# was_not_root_aerialboard_rev1.net
KiCad netlist of a schematic drawn in EAGLE
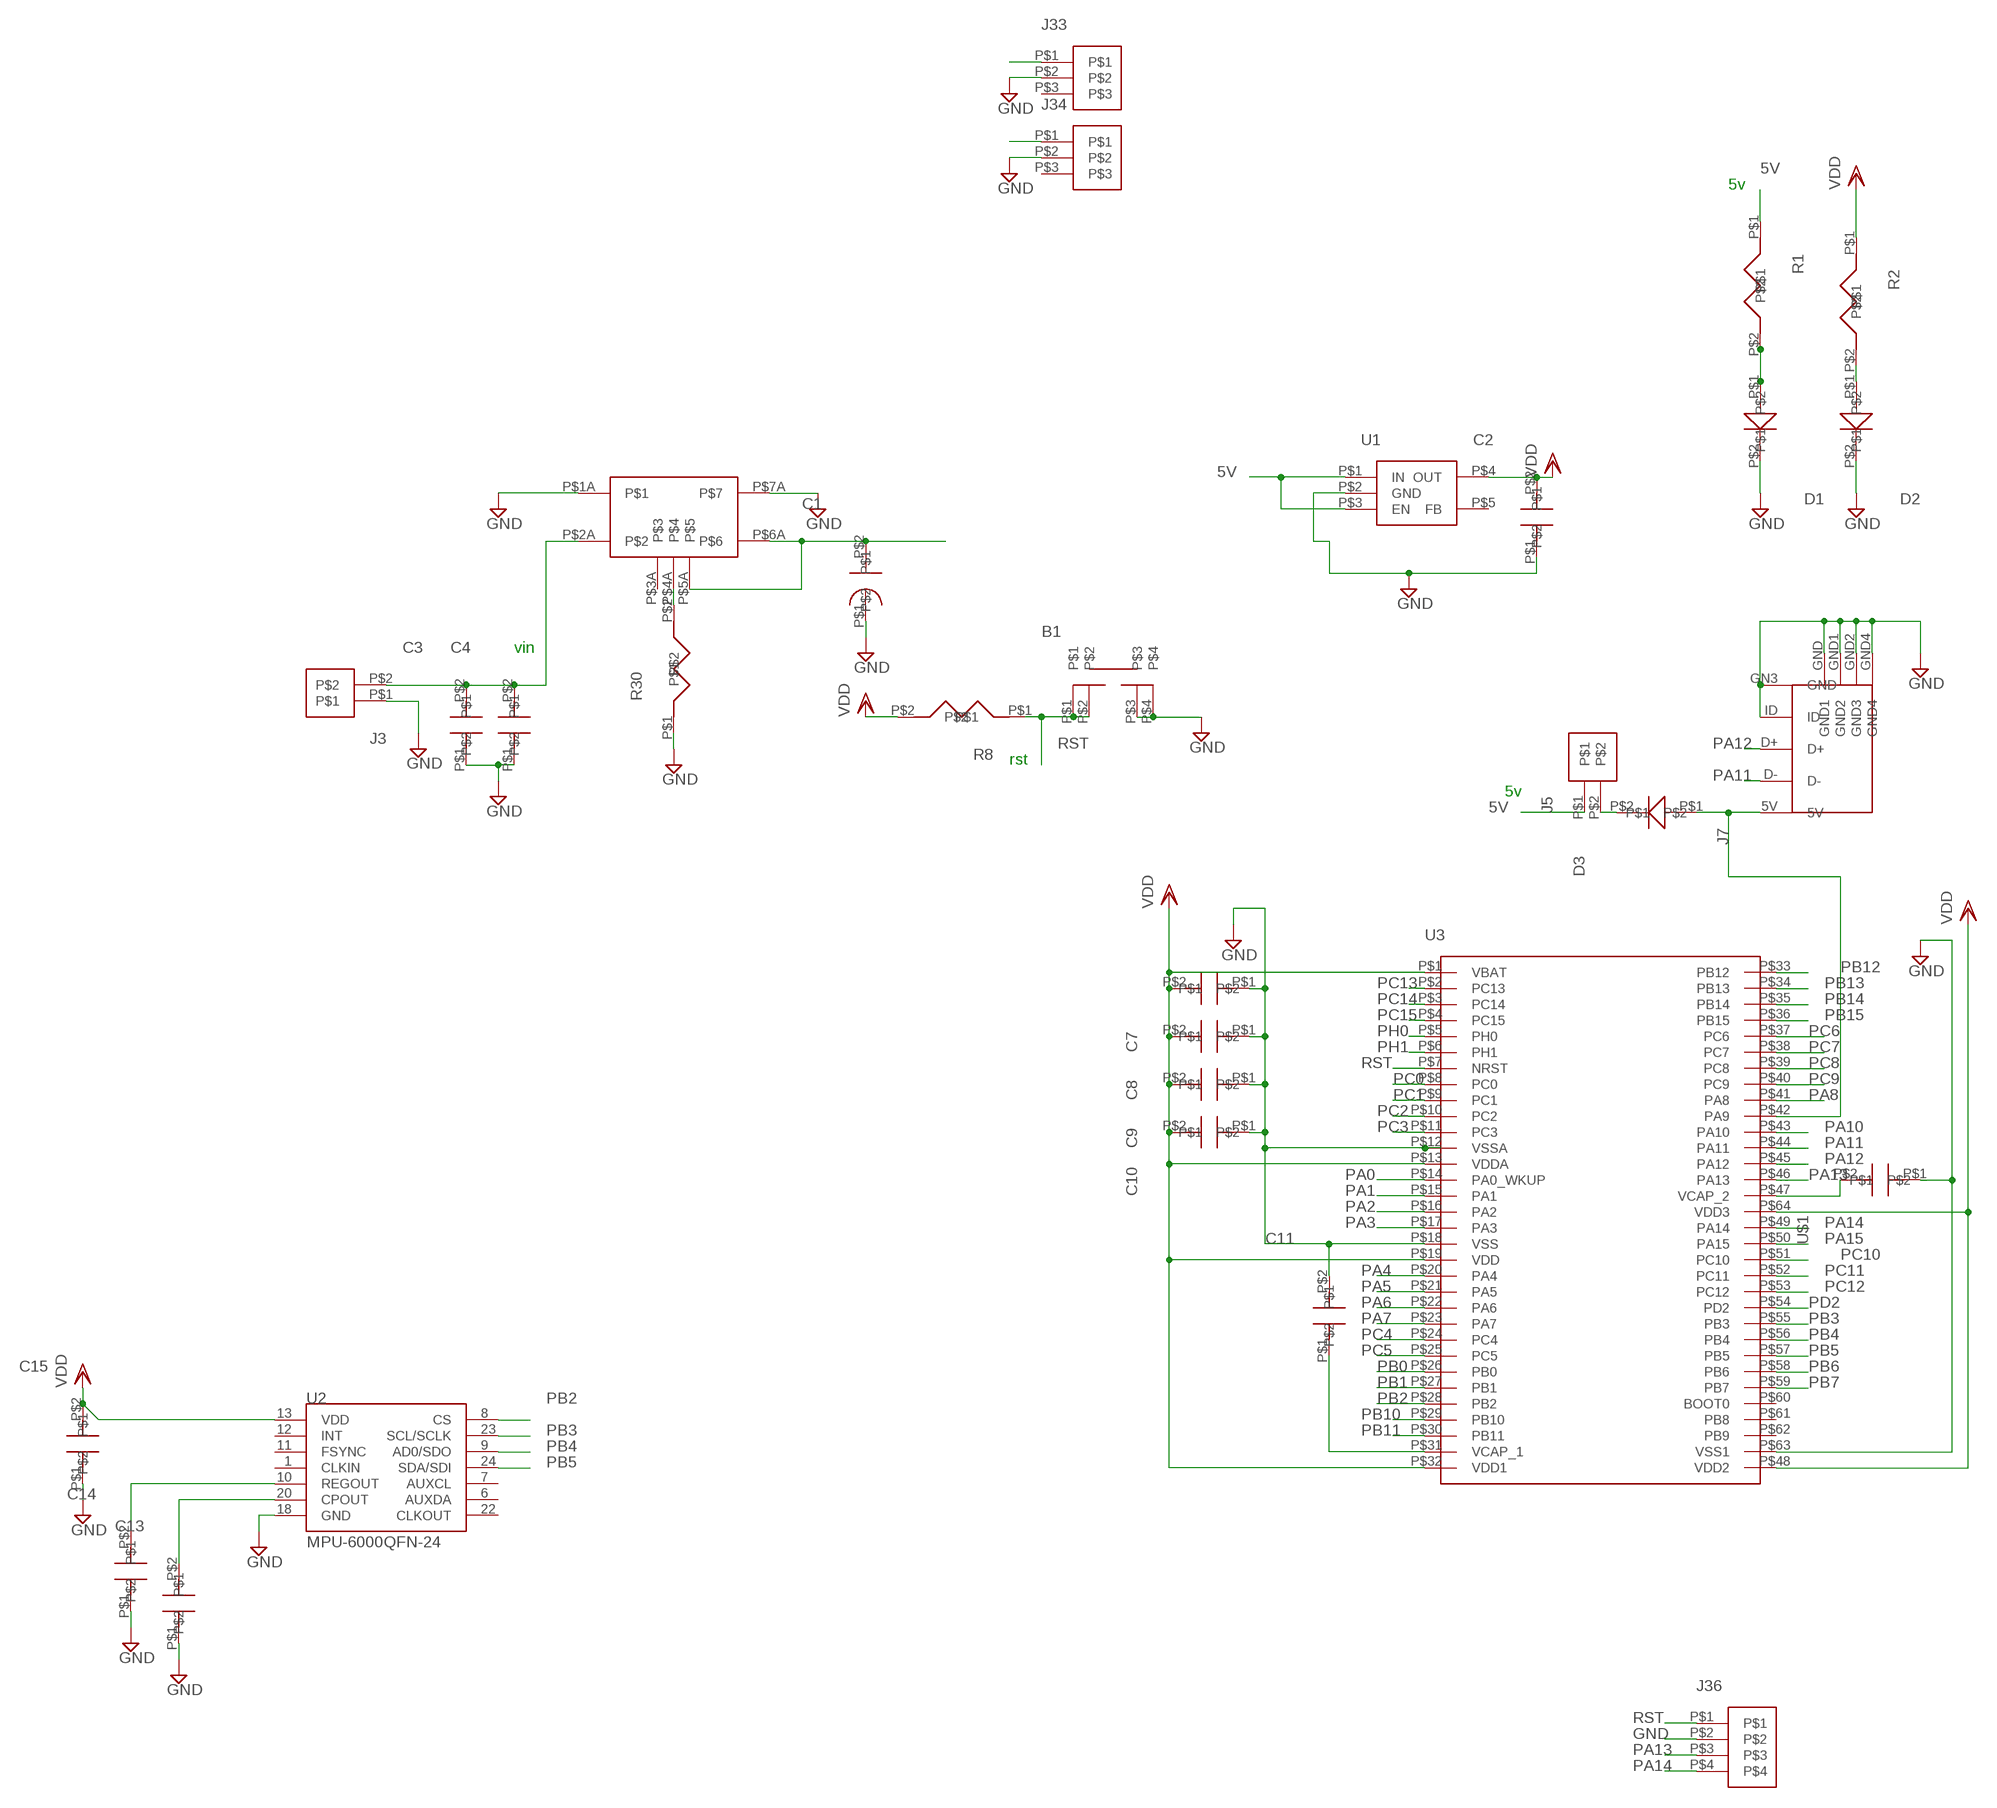
[diagram p0: schematic, sheet 1, part 1 of 2]
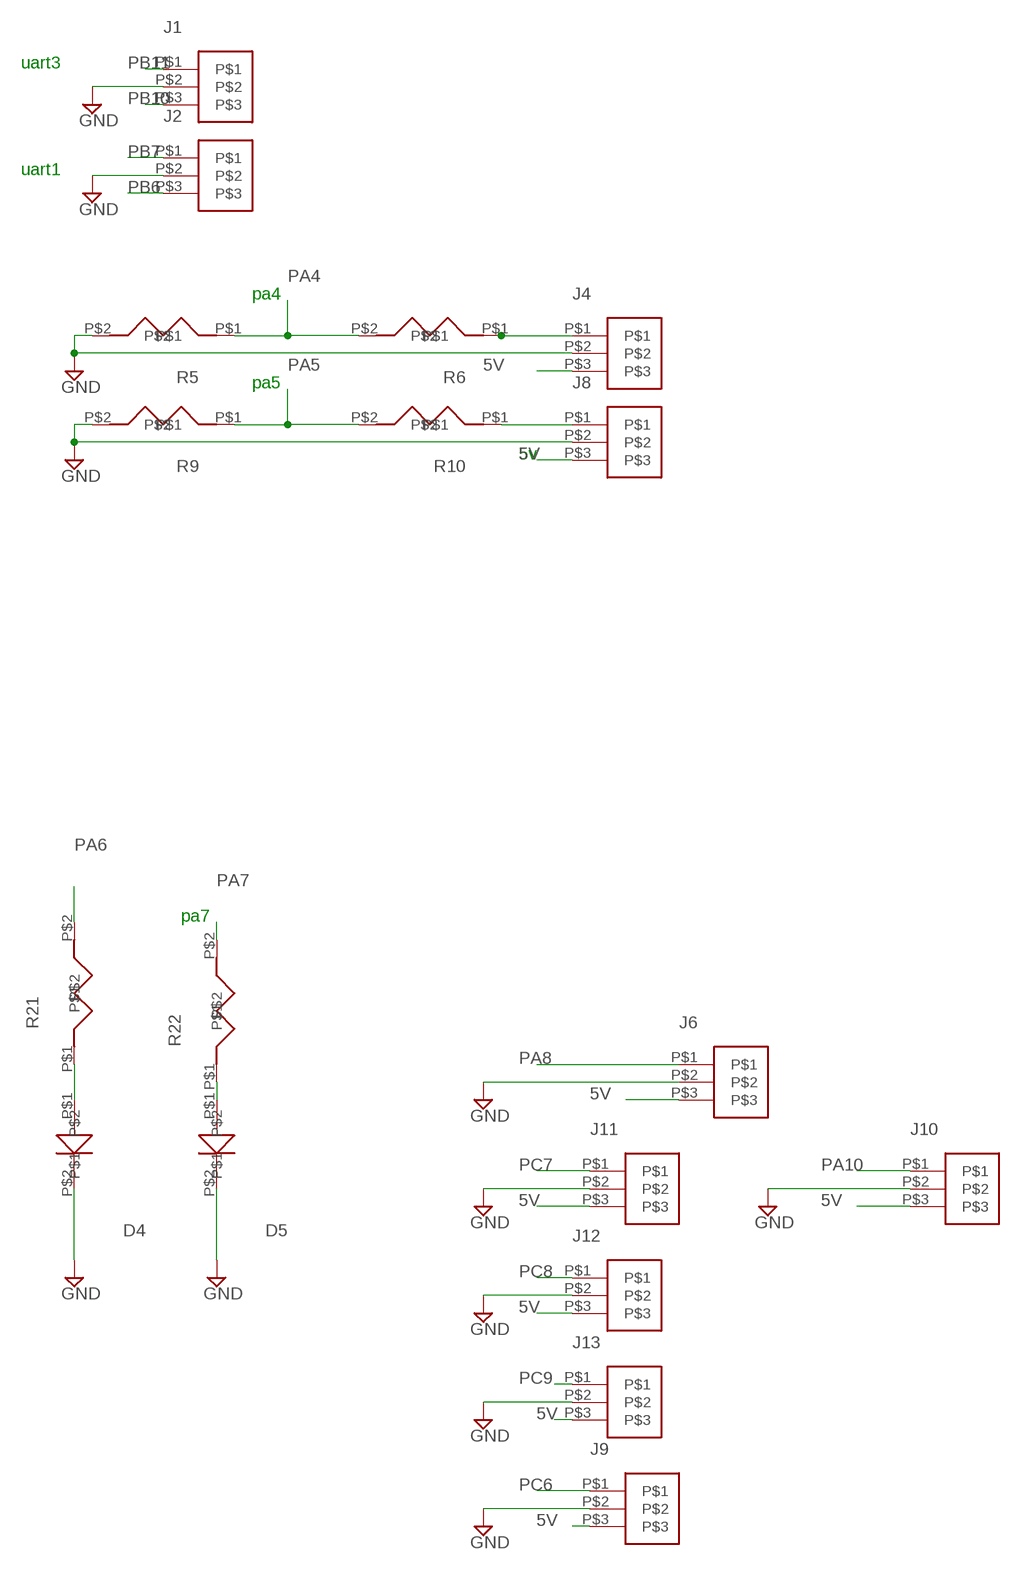
[diagram p1: schematic, sheet 1, part 2 of 2]

(export (version "E")
  (design (tool "Eeschema 10.0.6"))
  (components
    (comp (ref "B1")
      (value "SM-BUTTON")
      (footprint "eagle-import:SM_BUTTON")
      (libsource (lib "eagle-import") (part "SM-BUTTON"))
    )
    (comp (ref "C1")
      (value "CAPACITOR-330UF")
      (footprint "eagle-import:330UF-CAPACITOR")
      (libsource (lib "eagle-import") (part "CAPACITOR-330UF"))
    )
    (comp (ref "C2")
      (value "2.2UF-CAP")
      (footprint "eagle-import:0603-CAPACITOR")
      (libsource (lib "eagle-import") (part "2.2UF-CAP"))
    )
    (comp (ref "C3")
      (value "2.2UF-CAP")
      (footprint "eagle-import:0603-CAPACITOR")
      (libsource (lib "eagle-import") (part "2.2UF-CAP"))
    )
    (comp (ref "C4")
      (value "2.2UF-CAP")
      (footprint "eagle-import:0603-CAPACITOR")
      (libsource (lib "eagle-import") (part "2.2UF-CAP"))
    )
    (comp (ref "C7")
      (value "CAPACITOR-.1UF-4V")
      (footprint "eagle-import:0603-CAPACITOR")
      (libsource (lib "eagle-import") (part "CAPACITOR-.1UF-4V"))
    )
    (comp (ref "C8")
      (value "CAPACITOR-.1UF-4V")
      (footprint "eagle-import:0603-CAPACITOR")
      (libsource (lib "eagle-import") (part "CAPACITOR-.1UF-4V"))
    )
    (comp (ref "C9")
      (value "CAPACITOR-.1UF-4V")
      (footprint "eagle-import:0603-CAPACITOR")
      (libsource (lib "eagle-import") (part "CAPACITOR-.1UF-4V"))
    )
    (comp (ref "C10")
      (value "4.7UF-CAP6.3V")
      (footprint "eagle-import:0603-CAPACITOR")
      (libsource (lib "eagle-import") (part "4.7UF-CAP6.3V"))
    )
    (comp (ref "C11")
      (value "2.2UF-CAP")
      (footprint "eagle-import:0603-CAPACITOR")
      (libsource (lib "eagle-import") (part "2.2UF-CAP"))
    )
    (comp (ref "C13")
      (value "CAPACITOR-2.2NF-50V")
      (footprint "eagle-import:0603-CAPACITOR")
      (libsource (lib "eagle-import") (part "CAPACITOR-2.2NF-50V"))
    )
    (comp (ref "C14")
      (value "CAPACITOR-.1UF-4V")
      (footprint "eagle-import:0603-CAPACITOR")
      (libsource (lib "eagle-import") (part "CAPACITOR-.1UF-4V"))
    )
    (comp (ref "C15")
      (value "CAPACITOR-.1UF-4V")
      (footprint "eagle-import:0603-CAPACITOR")
      (libsource (lib "eagle-import") (part "CAPACITOR-.1UF-4V"))
    )
    (comp (ref "D1")
      (value "RED_LED")
      (footprint "eagle-import:0603-CAPACITOR")
      (libsource (lib "eagle-import") (part "RED_LED"))
    )
    (comp (ref "D2")
      (value "RED_LED")
      (footprint "eagle-import:0603-CAPACITOR")
      (libsource (lib "eagle-import") (part "RED_LED"))
    )
    (comp (ref "D3")
      (value "B240A-DIODE")
      (footprint "eagle-import:DIODE-DS13004")
      (libsource (lib "eagle-import") (part "B240A-DIODE"))
    )
    (comp (ref "D4")
      (value "RED_LED")
      (footprint "eagle-import:0603-CAPACITOR")
      (libsource (lib "eagle-import") (part "RED_LED"))
    )
    (comp (ref "D5")
      (value "ORANGE_LED")
      (footprint "eagle-import:0603-CAPACITOR")
      (libsource (lib "eagle-import") (part "ORANGE_LED"))
    )
    (comp (ref "J1")
      (value "3-PIN-SHERLOCK")
      (footprint "eagle-import:3-PIN-2MM")
      (libsource (lib "eagle-import") (part "3-PIN-SHERLOCK"))
    )
    (comp (ref "J2")
      (value "3-PIN-SHERLOCK")
      (footprint "eagle-import:3-PIN-2MM")
      (libsource (lib "eagle-import") (part "3-PIN-SHERLOCK"))
    )
    (comp (ref "J3")
      (value "2-PIN-POWER")
      (footprint "eagle-import:2-PIN-3MM")
      (libsource (lib "eagle-import") (part "2-PIN-POWER"))
    )
    (comp (ref "J4")
      (value "3-PIN-SHERLOCK")
      (footprint "eagle-import:3-PIN-2MM")
      (libsource (lib "eagle-import") (part "3-PIN-SHERLOCK"))
    )
    (comp (ref "J5")
      (value "2-PIN-100MIL")
      (footprint "eagle-import:2PIN-100MIL")
      (libsource (lib "eagle-import") (part "2-PIN-100MIL"))
    )
    (comp (ref "J6")
      (value "3-PIN-SHERLOCK")
      (footprint "eagle-import:3-PIN-2MM")
      (libsource (lib "eagle-import") (part "3-PIN-SHERLOCK"))
    )
    (comp (ref "J7")
      (value "USB_MINI_B")
      (footprint "eagle-import:USB_MINI_B")
      (libsource (lib "eagle-import") (part "USB_MINI_B"))
    )
    (comp (ref "J8")
      (value "3-PIN-SHERLOCK")
      (footprint "eagle-import:3-PIN-2MM")
      (libsource (lib "eagle-import") (part "3-PIN-SHERLOCK"))
    )
    (comp (ref "J9")
      (value "3-PIN-SHERLOCK")
      (footprint "eagle-import:3-PIN-2MM")
      (libsource (lib "eagle-import") (part "3-PIN-SHERLOCK"))
    )
    (comp (ref "J10")
      (value "3-PIN-SHERLOCK")
      (footprint "eagle-import:3-PIN-2MM")
      (libsource (lib "eagle-import") (part "3-PIN-SHERLOCK"))
    )
    (comp (ref "J11")
      (value "3-PIN-SHERLOCK")
      (footprint "eagle-import:3-PIN-2MM")
      (libsource (lib "eagle-import") (part "3-PIN-SHERLOCK"))
    )
    (comp (ref "J12")
      (value "3-PIN-SHERLOCK")
      (footprint "eagle-import:3-PIN-2MM")
      (libsource (lib "eagle-import") (part "3-PIN-SHERLOCK"))
    )
    (comp (ref "J13")
      (value "3-PIN-SHERLOCK")
      (footprint "eagle-import:3-PIN-2MM")
      (libsource (lib "eagle-import") (part "3-PIN-SHERLOCK"))
    )
    (comp (ref "J33")
      (value "3-PIN-3MM")
      (footprint "eagle-import:3-PIN-3MM")
      (libsource (lib "eagle-import") (part "3-PIN-3MM"))
    )
    (comp (ref "J34")
      (value "3-PIN-3MM")
      (footprint "eagle-import:3-PIN-3MM")
      (libsource (lib "eagle-import") (part "3-PIN-3MM"))
    )
    (comp (ref "J36")
      (value "4-PIN-SHERLOCK")
      (footprint "eagle-import:4-PIN-2MM")
      (libsource (lib "eagle-import") (part "4-PIN-SHERLOCK"))
    )
    (comp (ref "R1")
      (value "RESISTOR-4.7K-25V")
      (footprint "eagle-import:0603-CAPACITOR")
      (libsource (lib "eagle-import") (part "RESISTOR-4.7K-25V"))
    )
    (comp (ref "R2")
      (value "RESISTOR-4.7K-25V")
      (footprint "eagle-import:0603-CAPACITOR")
      (libsource (lib "eagle-import") (part "RESISTOR-4.7K-25V"))
    )
    (comp (ref "R5")
      (value "10K_RESISTOR")
      (footprint "eagle-import:0603-CAPACITOR")
      (libsource (lib "eagle-import") (part "10K_RESISTOR"))
    )
    (comp (ref "R6")
      (value "10K_RESISTOR")
      (footprint "eagle-import:0603-CAPACITOR")
      (libsource (lib "eagle-import") (part "10K_RESISTOR"))
    )
    (comp (ref "R8")
      (value "RESISTOR-4.7K-25V")
      (footprint "eagle-import:0603-CAPACITOR")
      (libsource (lib "eagle-import") (part "RESISTOR-4.7K-25V"))
    )
    (comp (ref "R9")
      (value "10K_RESISTOR")
      (footprint "eagle-import:0603-CAPACITOR")
      (libsource (lib "eagle-import") (part "10K_RESISTOR"))
    )
    (comp (ref "R10")
      (value "10K_RESISTOR")
      (footprint "eagle-import:0603-CAPACITOR")
      (libsource (lib "eagle-import") (part "10K_RESISTOR"))
    )
    (comp (ref "R21")
      (value "RESISTOR-4.7K-25V")
      (footprint "eagle-import:0603-CAPACITOR")
      (libsource (lib "eagle-import") (part "RESISTOR-4.7K-25V"))
    )
    (comp (ref "R22")
      (value "RESISTOR-4.7K-25V")
      (footprint "eagle-import:0603-CAPACITOR")
      (libsource (lib "eagle-import") (part "RESISTOR-4.7K-25V"))
    )
    (comp (ref "R30")
      (value "21K_RESISTOR")
      (footprint "eagle-import:0603-CAPACITOR")
      (libsource (lib "eagle-import") (part "21K_RESISTOR"))
    )
    (comp (ref "U$1")
      (value "2.2UF-CAP")
      (footprint "eagle-import:0603-CAPACITOR")
      (libsource (lib "eagle-import") (part "2.2UF-CAP"))
    )
    (comp (ref "U$2")
      (value "WIDE_IN_REG")
      (footprint "eagle-import:WIDE_IN_REG")
      (libsource (lib "eagle-import") (part "WIDE_IN_REG"))
    )
    (comp (ref "U1")
      (value "TPS73433-3.3-REG")
      (footprint "eagle-import:TPS73433-SOT5")
      (libsource (lib "eagle-import") (part "TPS73433-3.3-REG"))
    )
    (comp (ref "U2")
      (value "MPU-6000QFN-24")
      (footprint "eagle-import:QFN-24-TESTING")
      (libsource (lib "eagle-import") (part "MPU-6000QFN-24"))
    )
    (comp (ref "U3")
      (value "STM32F405RG")
      (footprint "eagle-import:LQFP-64-STM32F405")
      (libsource (lib "eagle-import") (part "STM32F405RG"))
    )
  )
  (nets
    (net (code "1") (name "/5V") (class "Default")
      (node (ref "C1") (pin "P$2") (pinfunction "P$2_P$2") (pintype "bidirectional"))
      (node (ref "J10") (pin "P$3") (pinfunction "P$3_P$3") (pintype "bidirectional"))
      (node (ref "J11") (pin "P$3") (pinfunction "P$3_P$3") (pintype "bidirectional"))
      (node (ref "J12") (pin "P$3") (pinfunction "P$3_P$3") (pintype "bidirectional"))
      (node (ref "J13") (pin "P$3") (pinfunction "P$3_P$3") (pintype "bidirectional"))
      (node (ref "J33") (pin "P$1") (pinfunction "P$1_P$1") (pintype "bidirectional"))
      (node (ref "J34") (pin "P$1") (pinfunction "P$1_P$1") (pintype "bidirectional"))
      (node (ref "J4") (pin "P$3") (pinfunction "P$3_P$3") (pintype "bidirectional"))
      (node (ref "J5") (pin "P$1") (pinfunction "P$1_P$1") (pintype "bidirectional"))
      (node (ref "J6") (pin "P$3") (pinfunction "P$3_P$3") (pintype "bidirectional"))
      (node (ref "J8") (pin "P$3") (pinfunction "P$3_P$3") (pintype "bidirectional"))
      (node (ref "J9") (pin "P$3") (pinfunction "P$3_P$3") (pintype "bidirectional"))
      (node (ref "R1") (pin "P$1") (pinfunction "P$1_P$1") (pintype "bidirectional"))
      (node (ref "U$2") (pin "P$5A") (pinfunction "P$5_P$5A") (pintype "bidirectional"))
      (node (ref "U$2") (pin "P$6A") (pinfunction "P$6_P$6A") (pintype "bidirectional"))
      (node (ref "U1") (pin "P$1") (pinfunction "IN_P$1") (pintype "bidirectional"))
      (node (ref "U1") (pin "P$3") (pinfunction "EN_P$3") (pintype "bidirectional"))
    )
    (net (code "2") (name "/PA0") (class "Default")
      (node (ref "U3") (pin "P$14") (pinfunction "PA0_WKUP_P$14") (pintype "bidirectional"))
    )
    (net (code "3") (name "/PA1") (class "Default")
      (node (ref "U3") (pin "P$15") (pinfunction "PA1_P$15") (pintype "bidirectional"))
    )
    (net (code "4") (name "/PA2") (class "Default")
      (node (ref "U3") (pin "P$16") (pinfunction "PA2_P$16") (pintype "bidirectional"))
    )
    (net (code "5") (name "/PA3") (class "Default")
      (node (ref "U3") (pin "P$17") (pinfunction "PA3_P$17") (pintype "bidirectional"))
    )
    (net (code "6") (name "/PA4") (class "Default")
      (node (ref "R5") (pin "P$1") (pinfunction "P$1_P$1") (pintype "bidirectional"))
      (node (ref "R6") (pin "P$2") (pinfunction "P$2_P$2") (pintype "bidirectional"))
      (node (ref "U3") (pin "P$20") (pinfunction "PA4_P$20") (pintype "bidirectional"))
    )
    (net (code "7") (name "/PA5") (class "Default")
      (node (ref "R10") (pin "P$2") (pinfunction "P$2_P$2") (pintype "bidirectional"))
      (node (ref "R9") (pin "P$1") (pinfunction "P$1_P$1") (pintype "bidirectional"))
      (node (ref "U3") (pin "P$21") (pinfunction "PA5_P$21") (pintype "bidirectional"))
    )
    (net (code "8") (name "/PA6") (class "Default")
      (node (ref "R21") (pin "P$2") (pinfunction "P$2_P$2") (pintype "bidirectional"))
      (node (ref "U3") (pin "P$22") (pinfunction "PA6_P$22") (pintype "bidirectional"))
    )
    (net (code "9") (name "/PA7") (class "Default")
      (node (ref "R22") (pin "P$2") (pinfunction "P$2_P$2") (pintype "bidirectional"))
      (node (ref "U3") (pin "P$23") (pinfunction "PA7_P$23") (pintype "bidirectional"))
    )
    (net (code "10") (name "/PA8") (class "Default")
      (node (ref "J6") (pin "P$1") (pinfunction "P$1_P$1") (pintype "bidirectional"))
      (node (ref "U3") (pin "P$41") (pinfunction "PA8_P$41") (pintype "bidirectional"))
    )
    (net (code "11") (name "/PA10") (class "Default")
      (node (ref "J10") (pin "P$1") (pinfunction "P$1_P$1") (pintype "bidirectional"))
      (node (ref "U3") (pin "P$43") (pinfunction "PA10_P$43") (pintype "bidirectional"))
    )
    (net (code "12") (name "/PA11") (class "Default")
      (node (ref "J7") (pin "D-") (pinfunction "D-_D-") (pintype "bidirectional"))
      (node (ref "U3") (pin "P$44") (pinfunction "PA11_P$44") (pintype "bidirectional"))
    )
    (net (code "13") (name "/PA12") (class "Default")
      (node (ref "J7") (pin "D+") (pinfunction "D+_D+") (pintype "bidirectional"))
      (node (ref "U3") (pin "P$45") (pinfunction "PA12_P$45") (pintype "bidirectional"))
    )
    (net (code "14") (name "/PA13") (class "Default")
      (node (ref "J36") (pin "P$3") (pinfunction "P$3_P$3") (pintype "bidirectional"))
      (node (ref "U3") (pin "P$46") (pinfunction "PA13_P$46") (pintype "bidirectional"))
    )
    (net (code "15") (name "/PA14") (class "Default")
      (node (ref "J36") (pin "P$4") (pinfunction "P$4_P$4") (pintype "bidirectional"))
      (node (ref "U3") (pin "P$49") (pinfunction "PA14_P$49") (pintype "bidirectional"))
    )
    (net (code "16") (name "/PA15") (class "Default")
      (node (ref "U3") (pin "P$50") (pinfunction "PA15_P$50") (pintype "bidirectional"))
    )
    (net (code "17") (name "/PB0") (class "Default")
      (node (ref "U3") (pin "P$26") (pinfunction "PB0_P$26") (pintype "bidirectional"))
    )
    (net (code "18") (name "/PB1") (class "Default")
      (node (ref "U3") (pin "P$27") (pinfunction "PB1_P$27") (pintype "bidirectional"))
    )
    (net (code "19") (name "/PB2") (class "Default")
      (node (ref "U2") (pin "8") (pinfunction "CS_8") (pintype "bidirectional"))
      (node (ref "U3") (pin "P$28") (pinfunction "PB2_P$28") (pintype "bidirectional"))
    )
    (net (code "20") (name "/PB3") (class "Default")
      (node (ref "U2") (pin "23") (pinfunction "SCL/SCLK_23") (pintype "bidirectional"))
      (node (ref "U3") (pin "P$55") (pinfunction "PB3_P$55") (pintype "bidirectional"))
    )
    (net (code "21") (name "/PB4") (class "Default")
      (node (ref "U2") (pin "9") (pinfunction "AD0/SDO_9") (pintype "bidirectional"))
      (node (ref "U3") (pin "P$56") (pinfunction "PB4_P$56") (pintype "bidirectional"))
    )
    (net (code "22") (name "/PB5") (class "Default")
      (node (ref "U2") (pin "24") (pinfunction "SDA/SDI_24") (pintype "bidirectional"))
      (node (ref "U3") (pin "P$57") (pinfunction "PB5_P$57") (pintype "bidirectional"))
    )
    (net (code "23") (name "/PB6") (class "Default")
      (node (ref "J2") (pin "P$3") (pinfunction "P$3_P$3") (pintype "bidirectional"))
      (node (ref "U3") (pin "P$58") (pinfunction "PB6_P$58") (pintype "bidirectional"))
    )
    (net (code "24") (name "/PB7") (class "Default")
      (node (ref "J2") (pin "P$1") (pinfunction "P$1_P$1") (pintype "bidirectional"))
      (node (ref "U3") (pin "P$59") (pinfunction "PB7_P$59") (pintype "bidirectional"))
    )
    (net (code "25") (name "/PB10") (class "Default")
      (node (ref "J1") (pin "P$3") (pinfunction "P$3_P$3") (pintype "bidirectional"))
      (node (ref "U3") (pin "P$29") (pinfunction "PB10_P$29") (pintype "bidirectional"))
    )
    (net (code "26") (name "/PB11") (class "Default")
      (node (ref "J1") (pin "P$1") (pinfunction "P$1_P$1") (pintype "bidirectional"))
      (node (ref "U3") (pin "P$30") (pinfunction "PB11_P$30") (pintype "bidirectional"))
    )
    (net (code "27") (name "/PB12") (class "Default")
      (node (ref "U3") (pin "P$33") (pinfunction "PB12_P$33") (pintype "bidirectional"))
    )
    (net (code "28") (name "/PB13") (class "Default")
      (node (ref "U3") (pin "P$34") (pinfunction "PB13_P$34") (pintype "bidirectional"))
    )
    (net (code "29") (name "/PB14") (class "Default")
      (node (ref "U3") (pin "P$35") (pinfunction "PB14_P$35") (pintype "bidirectional"))
    )
    (net (code "30") (name "/PB15") (class "Default")
      (node (ref "U3") (pin "P$36") (pinfunction "PB15_P$36") (pintype "bidirectional"))
    )
    (net (code "31") (name "/PC0") (class "Default")
      (node (ref "U3") (pin "P$8") (pinfunction "PC0_P$8") (pintype "bidirectional"))
    )
    (net (code "32") (name "/PC1") (class "Default")
      (node (ref "U3") (pin "P$9") (pinfunction "PC1_P$9") (pintype "bidirectional"))
    )
    (net (code "33") (name "/PC2") (class "Default")
      (node (ref "U3") (pin "P$10") (pinfunction "PC2_P$10") (pintype "bidirectional"))
    )
    (net (code "34") (name "/PC3") (class "Default")
      (node (ref "U3") (pin "P$11") (pinfunction "PC3_P$11") (pintype "bidirectional"))
    )
    (net (code "35") (name "/PC4") (class "Default")
      (node (ref "U3") (pin "P$24") (pinfunction "PC4_P$24") (pintype "bidirectional"))
    )
    (net (code "36") (name "/PC5") (class "Default")
      (node (ref "U3") (pin "P$25") (pinfunction "PC5_P$25") (pintype "bidirectional"))
    )
    (net (code "37") (name "/PC6") (class "Default")
      (node (ref "J9") (pin "P$1") (pinfunction "P$1_P$1") (pintype "bidirectional"))
      (node (ref "U3") (pin "P$37") (pinfunction "PC6_P$37") (pintype "bidirectional"))
    )
    (net (code "38") (name "/PC7") (class "Default")
      (node (ref "J11") (pin "P$1") (pinfunction "P$1_P$1") (pintype "bidirectional"))
      (node (ref "U3") (pin "P$38") (pinfunction "PC7_P$38") (pintype "bidirectional"))
    )
    (net (code "39") (name "/PC8") (class "Default")
      (node (ref "J12") (pin "P$1") (pinfunction "P$1_P$1") (pintype "bidirectional"))
      (node (ref "U3") (pin "P$39") (pinfunction "PC8_P$39") (pintype "bidirectional"))
    )
    (net (code "40") (name "/PC9") (class "Default")
      (node (ref "J13") (pin "P$1") (pinfunction "P$1_P$1") (pintype "bidirectional"))
      (node (ref "U3") (pin "P$40") (pinfunction "PC9_P$40") (pintype "bidirectional"))
    )
    (net (code "41") (name "/PC10") (class "Default")
      (node (ref "U3") (pin "P$51") (pinfunction "PC10_P$51") (pintype "bidirectional"))
    )
    (net (code "42") (name "/PC11") (class "Default")
      (node (ref "U3") (pin "P$52") (pinfunction "PC11_P$52") (pintype "bidirectional"))
    )
    (net (code "43") (name "/PC12") (class "Default")
      (node (ref "U3") (pin "P$53") (pinfunction "PC12_P$53") (pintype "bidirectional"))
    )
    (net (code "44") (name "/PC13") (class "Default")
      (node (ref "U3") (pin "P$2") (pinfunction "PC13_P$2") (pintype "bidirectional"))
    )
    (net (code "45") (name "/PC14") (class "Default")
      (node (ref "U3") (pin "P$3") (pinfunction "PC14_P$3") (pintype "bidirectional"))
    )
    (net (code "46") (name "/PC15") (class "Default")
      (node (ref "U3") (pin "P$4") (pinfunction "PC15_P$4") (pintype "bidirectional"))
    )
    (net (code "47") (name "/PD2") (class "Default")
      (node (ref "U3") (pin "P$54") (pinfunction "PD2_P$54") (pintype "bidirectional"))
    )
    (net (code "48") (name "/PH0") (class "Default")
      (node (ref "U3") (pin "P$5") (pinfunction "PH0_P$5") (pintype "bidirectional"))
    )
    (net (code "49") (name "/PH1") (class "Default")
      (node (ref "U3") (pin "P$6") (pinfunction "PH1_P$6") (pintype "bidirectional"))
    )
    (net (code "50") (name "/RST") (class "Default")
      (node (ref "B1") (pin "P$1") (pinfunction "P$1_P$1") (pintype "bidirectional"))
      (node (ref "B1") (pin "P$2") (pinfunction "P$2_P$2") (pintype "bidirectional"))
      (node (ref "J36") (pin "P$1") (pinfunction "P$1_P$1") (pintype "bidirectional"))
      (node (ref "R8") (pin "P$1") (pinfunction "P$1_P$1") (pintype "bidirectional"))
      (node (ref "U3") (pin "P$7") (pinfunction "NRST_P$7") (pintype "bidirectional"))
    )
    (net (code "51") (name "GND") (class "Default")
      (node (ref "B1") (pin "P$3") (pinfunction "P$3_P$3") (pintype "bidirectional"))
      (node (ref "B1") (pin "P$4") (pinfunction "P$4_P$4") (pintype "bidirectional"))
      (node (ref "C1") (pin "P$1") (pinfunction "P$1_P$1") (pintype "bidirectional"))
      (node (ref "C10") (pin "P$1") (pinfunction "P$1_P$1") (pintype "bidirectional"))
      (node (ref "C11") (pin "P$2") (pinfunction "P$2_P$2") (pintype "bidirectional"))
      (node (ref "C13") (pin "P$1") (pinfunction "P$1_P$1") (pintype "bidirectional"))
      (node (ref "C14") (pin "P$1") (pinfunction "P$1_P$1") (pintype "bidirectional"))
      (node (ref "C15") (pin "P$1") (pinfunction "P$1_P$1") (pintype "bidirectional"))
      (node (ref "C2") (pin "P$1") (pinfunction "P$1_P$1") (pintype "bidirectional"))
      (node (ref "C3") (pin "P$1") (pinfunction "P$1_P$1") (pintype "bidirectional"))
      (node (ref "C4") (pin "P$1") (pinfunction "P$1_P$1") (pintype "bidirectional"))
      (node (ref "C7") (pin "P$1") (pinfunction "P$1_P$1") (pintype "bidirectional"))
      (node (ref "C8") (pin "P$1") (pinfunction "P$1_P$1") (pintype "bidirectional"))
      (node (ref "C9") (pin "P$1") (pinfunction "P$1_P$1") (pintype "bidirectional"))
      (node (ref "D1") (pin "P$2") (pinfunction "P$2_P$2") (pintype "bidirectional"))
      (node (ref "D2") (pin "P$2") (pinfunction "P$2_P$2") (pintype "bidirectional"))
      (node (ref "D4") (pin "P$2") (pinfunction "P$2_P$2") (pintype "bidirectional"))
      (node (ref "D5") (pin "P$2") (pinfunction "P$2_P$2") (pintype "bidirectional"))
      (node (ref "J1") (pin "P$2") (pinfunction "P$2_P$2") (pintype "bidirectional"))
      (node (ref "J10") (pin "P$2") (pinfunction "P$2_P$2") (pintype "bidirectional"))
      (node (ref "J11") (pin "P$2") (pinfunction "P$2_P$2") (pintype "bidirectional"))
      (node (ref "J12") (pin "P$2") (pinfunction "P$2_P$2") (pintype "bidirectional"))
      (node (ref "J13") (pin "P$2") (pinfunction "P$2_P$2") (pintype "bidirectional"))
      (node (ref "J2") (pin "P$2") (pinfunction "P$2_P$2") (pintype "bidirectional"))
      (node (ref "J3") (pin "P$1") (pinfunction "P$1_P$1") (pintype "bidirectional"))
      (node (ref "J33") (pin "P$2") (pinfunction "P$2_P$2") (pintype "bidirectional"))
      (node (ref "J34") (pin "P$2") (pinfunction "P$2_P$2") (pintype "bidirectional"))
      (node (ref "J36") (pin "P$2") (pinfunction "P$2_P$2") (pintype "bidirectional"))
      (node (ref "J4") (pin "P$2") (pinfunction "P$2_P$2") (pintype "bidirectional"))
      (node (ref "J6") (pin "P$2") (pinfunction "P$2_P$2") (pintype "bidirectional"))
      (node (ref "J7") (pin "GN3") (pinfunction "GND_GN3") (pintype "bidirectional"))
      (node (ref "J7") (pin "GND") (pinfunction "GND1_GND") (pintype "bidirectional"))
      (node (ref "J7") (pin "GND1") (pinfunction "GND2_GND1") (pintype "bidirectional"))
      (node (ref "J7") (pin "GND2") (pinfunction "GND3_GND2") (pintype "bidirectional"))
      (node (ref "J7") (pin "GND4") (pinfunction "GND4_GND4") (pintype "bidirectional"))
      (node (ref "J7") (pin "ID") (pinfunction "ID_ID") (pintype "bidirectional"))
      (node (ref "J8") (pin "P$2") (pinfunction "P$2_P$2") (pintype "bidirectional"))
      (node (ref "J9") (pin "P$2") (pinfunction "P$2_P$2") (pintype "bidirectional"))
      (node (ref "R30") (pin "P$1") (pinfunction "P$1_P$1") (pintype "bidirectional"))
      (node (ref "R5") (pin "P$2") (pinfunction "P$2_P$2") (pintype "bidirectional"))
      (node (ref "R9") (pin "P$2") (pinfunction "P$2_P$2") (pintype "bidirectional"))
      (node (ref "U$1") (pin "P$1") (pinfunction "P$1_P$1") (pintype "bidirectional"))
      (node (ref "U$2") (pin "P$1A") (pinfunction "P$1_P$1A") (pintype "bidirectional"))
      (node (ref "U$2") (pin "P$7A") (pinfunction "P$7_P$7A") (pintype "bidirectional"))
      (node (ref "U1") (pin "P$2") (pinfunction "GND_P$2") (pintype "bidirectional"))
      (node (ref "U2") (pin "18") (pinfunction "GND_18") (pintype "bidirectional"))
      (node (ref "U3") (pin "P$12") (pinfunction "VSSA_P$12") (pintype "bidirectional"))
      (node (ref "U3") (pin "P$18") (pinfunction "VSS_P$18") (pintype "bidirectional"))
      (node (ref "U3") (pin "P$63") (pinfunction "VSS1_P$63") (pintype "bidirectional"))
    )
    (net (code "52") (name "Net-(D1-PadP$1)") (class "Default")
      (node (ref "D1") (pin "P$1") (pinfunction "P$1_P$1") (pintype "bidirectional"))
      (node (ref "R1") (pin "P$2") (pinfunction "P$2_P$2") (pintype "bidirectional"))
    )
    (net (code "53") (name "Net-(D2-PadP$1)") (class "Default")
      (node (ref "D2") (pin "P$1") (pinfunction "P$1_P$1") (pintype "bidirectional"))
      (node (ref "R2") (pin "P$2") (pinfunction "P$2_P$2") (pintype "bidirectional"))
    )
    (net (code "54") (name "Net-(D3-PadP$2)") (class "Default")
      (node (ref "D3") (pin "P$2") (pinfunction "P$2_P$2") (pintype "bidirectional"))
      (node (ref "J5") (pin "P$2") (pinfunction "P$2_P$2") (pintype "bidirectional"))
    )
    (net (code "55") (name "Net-(D4-PadP$1)") (class "Default")
      (node (ref "D4") (pin "P$1") (pinfunction "P$1_P$1") (pintype "bidirectional"))
      (node (ref "R21") (pin "P$1") (pinfunction "P$1_P$1") (pintype "bidirectional"))
    )
    (net (code "56") (name "Net-(D5-PadP$1)") (class "Default")
      (node (ref "D5") (pin "P$1") (pinfunction "P$1_P$1") (pintype "bidirectional"))
      (node (ref "R22") (pin "P$1") (pinfunction "P$1_P$1") (pintype "bidirectional"))
    )
    (net (code "57") (name "Net-(J4-PadP$1)") (class "Default")
      (node (ref "J4") (pin "P$1") (pinfunction "P$1_P$1") (pintype "bidirectional"))
      (node (ref "R6") (pin "P$1") (pinfunction "P$1_P$1") (pintype "bidirectional"))
    )
    (net (code "58") (name "Net-(J8-PadP$1)") (class "Default")
      (node (ref "J8") (pin "P$1") (pinfunction "P$1_P$1") (pintype "bidirectional"))
      (node (ref "R10") (pin "P$1") (pinfunction "P$1_P$1") (pintype "bidirectional"))
    )
    (net (code "59") (name "Net-(U$2-P$2)") (class "Default")
      (node (ref "C3") (pin "P$2") (pinfunction "P$2_P$2") (pintype "bidirectional"))
      (node (ref "C4") (pin "P$2") (pinfunction "P$2_P$2") (pintype "bidirectional"))
      (node (ref "J3") (pin "P$2") (pinfunction "P$2_P$2") (pintype "bidirectional"))
      (node (ref "U$2") (pin "P$2A") (pinfunction "P$2_P$2A") (pintype "bidirectional"))
    )
    (net (code "60") (name "Net-(U$2-P$4)") (class "Default")
      (node (ref "R30") (pin "P$2") (pinfunction "P$2_P$2") (pintype "bidirectional"))
      (node (ref "U$2") (pin "P$4A") (pinfunction "P$4_P$4A") (pintype "bidirectional"))
    )
    (net (code "61") (name "Net-(U2-CPOUT)") (class "Default")
      (node (ref "C13") (pin "P$2") (pinfunction "P$2_P$2") (pintype "bidirectional"))
      (node (ref "U2") (pin "20") (pinfunction "CPOUT_20") (pintype "bidirectional"))
    )
    (net (code "62") (name "Net-(U2-REGOUT)") (class "Default")
      (node (ref "C14") (pin "P$2") (pinfunction "P$2_P$2") (pintype "bidirectional"))
      (node (ref "U2") (pin "10") (pinfunction "REGOUT_10") (pintype "bidirectional"))
    )
    (net (code "63") (name "Net-(U3-PA9)") (class "Default")
      (node (ref "D3") (pin "P$1") (pinfunction "P$1_P$1") (pintype "bidirectional"))
      (node (ref "J7") (pin "5V") (pinfunction "5V_5V") (pintype "bidirectional"))
      (node (ref "U3") (pin "P$42") (pinfunction "PA9_P$42") (pintype "bidirectional"))
    )
    (net (code "64") (name "Net-(U3-VCAP_1)") (class "Default")
      (node (ref "C11") (pin "P$1") (pinfunction "P$1_P$1") (pintype "bidirectional"))
      (node (ref "U3") (pin "P$31") (pinfunction "VCAP_1_P$31") (pintype "bidirectional"))
    )
    (net (code "65") (name "Net-(U3-VCAP_2)") (class "Default")
      (node (ref "U$1") (pin "P$2") (pinfunction "P$2_P$2") (pintype "bidirectional"))
      (node (ref "U3") (pin "P$47") (pinfunction "VCAP_2_P$47") (pintype "bidirectional"))
    )
    (net (code "66") (name "VDD") (class "Default")
      (node (ref "C10") (pin "P$2") (pinfunction "P$2_P$2") (pintype "bidirectional"))
      (node (ref "C15") (pin "P$2") (pinfunction "P$2_P$2") (pintype "bidirectional"))
      (node (ref "C2") (pin "P$2") (pinfunction "P$2_P$2") (pintype "bidirectional"))
      (node (ref "C7") (pin "P$2") (pinfunction "P$2_P$2") (pintype "bidirectional"))
      (node (ref "C8") (pin "P$2") (pinfunction "P$2_P$2") (pintype "bidirectional"))
      (node (ref "C9") (pin "P$2") (pinfunction "P$2_P$2") (pintype "bidirectional"))
      (node (ref "R2") (pin "P$1") (pinfunction "P$1_P$1") (pintype "bidirectional"))
      (node (ref "R8") (pin "P$2") (pinfunction "P$2_P$2") (pintype "bidirectional"))
      (node (ref "U1") (pin "P$4") (pinfunction "OUT_P$4") (pintype "bidirectional"))
      (node (ref "U2") (pin "13") (pinfunction "VDD_13") (pintype "bidirectional"))
      (node (ref "U3") (pin "P$1") (pinfunction "VBAT_P$1") (pintype "bidirectional"))
      (node (ref "U3") (pin "P$13") (pinfunction "VDDA_P$13") (pintype "bidirectional"))
      (node (ref "U3") (pin "P$19") (pinfunction "VDD_P$19") (pintype "bidirectional"))
      (node (ref "U3") (pin "P$32") (pinfunction "VDD1_P$32") (pintype "bidirectional"))
      (node (ref "U3") (pin "P$48") (pinfunction "VDD2_P$48") (pintype "bidirectional"))
      (node (ref "U3") (pin "P$64") (pinfunction "VDD3_P$64") (pintype "bidirectional"))
    )
    (net (code "67") (name "unconnected-(J33-PadP$3)") (class "Default")
      (node (ref "J33") (pin "P$3") (pinfunction "P$3_P$3") (pintype "bidirectional"))
    )
    (net (code "68") (name "unconnected-(J34-PadP$3)") (class "Default")
      (node (ref "J34") (pin "P$3") (pinfunction "P$3_P$3") (pintype "bidirectional"))
    )
    (net (code "69") (name "unconnected-(U$2-P$3-PadP$3A)") (class "Default")
      (node (ref "U$2") (pin "P$3A") (pinfunction "P$3_P$3A") (pintype "bidirectional"))
    )
    (net (code "70") (name "unconnected-(U1-FB-PadP$5)") (class "Default")
      (node (ref "U1") (pin "P$5") (pinfunction "FB_P$5") (pintype "bidirectional"))
    )
    (net (code "71") (name "unconnected-(U2-AUXCL-Pad7)") (class "Default")
      (node (ref "U2") (pin "7") (pinfunction "AUXCL_7") (pintype "bidirectional"))
    )
    (net (code "72") (name "unconnected-(U2-AUXDA-Pad6)") (class "Default")
      (node (ref "U2") (pin "6") (pinfunction "AUXDA_6") (pintype "bidirectional"))
    )
    (net (code "73") (name "unconnected-(U2-CLKIN-Pad1)") (class "Default")
      (node (ref "U2") (pin "1") (pinfunction "CLKIN_1") (pintype "bidirectional"))
    )
    (net (code "74") (name "unconnected-(U2-CLKOUT-Pad22)") (class "Default")
      (node (ref "U2") (pin "22") (pinfunction "CLKOUT_22") (pintype "bidirectional"))
    )
    (net (code "75") (name "unconnected-(U2-FSYNC-Pad11)") (class "Default")
      (node (ref "U2") (pin "11") (pinfunction "FSYNC_11") (pintype "bidirectional"))
    )
    (net (code "76") (name "unconnected-(U2-INT-Pad12)") (class "Default")
      (node (ref "U2") (pin "12") (pinfunction "INT_12") (pintype "bidirectional"))
    )
    (net (code "77") (name "unconnected-(U3-BOOT0-PadP$60)") (class "Default")
      (node (ref "U3") (pin "P$60") (pinfunction "BOOT0_P$60") (pintype "bidirectional"))
    )
    (net (code "78") (name "unconnected-(U3-PB8-PadP$61)") (class "Default")
      (node (ref "U3") (pin "P$61") (pinfunction "PB8_P$61") (pintype "bidirectional"))
    )
    (net (code "79") (name "unconnected-(U3-PB9-PadP$62)") (class "Default")
      (node (ref "U3") (pin "P$62") (pinfunction "PB9_P$62") (pintype "bidirectional"))
    )
  )
)
